# Communication.net
KiCad netlist of a schematic drawn in Altium Designer
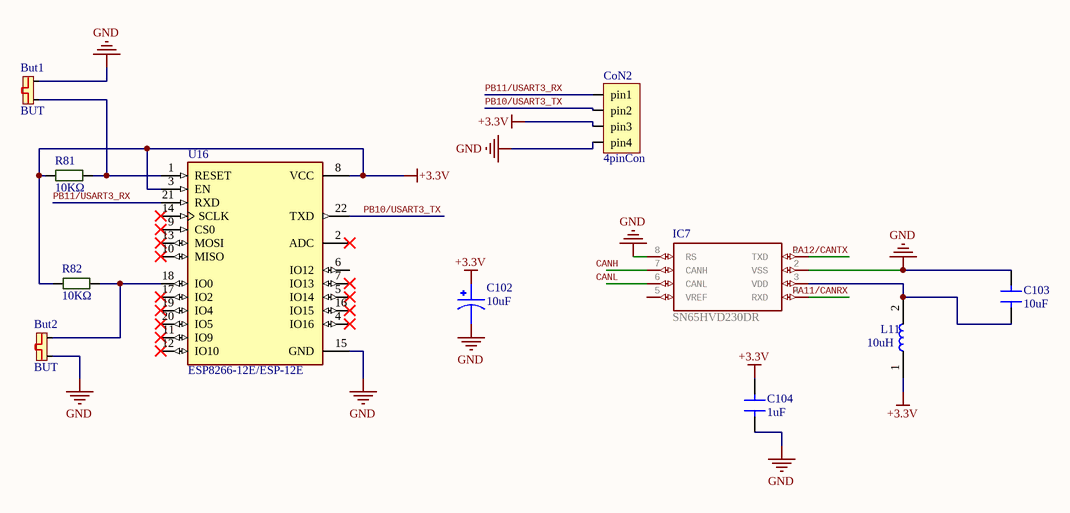
[diagram p0: Communication.SchDoc]

(export (version "E")
  (design (tool "Eeschema 10.0.6"))
  (components
    (comp (ref "But1") (value "BUT") (footprint "ButTON") (libsource (lib "Gate Driver Board") (part "BUT")))
    (comp (ref "But2") (value "BUT") (footprint "ButTON") (libsource (lib "Gate Driver Board") (part "BUT")))
    (comp (ref "C102")
      (value "10uF")
      (footprint "CapSmdElc")
      (libsource (lib "PROJE") (part "100 uF Electr Cap"))
    )
    (comp (ref "C103")
      (value "10uF")
      (footprint "C-0805")
      (libsource (lib "Gate Driver Board") (part "C-0805"))
    )
    (comp (ref "C104")
      (value "1uF")
      (footprint "C-0603W")
      (libsource (lib "Gate Driver Board") (part "C-0603"))
    )
    (comp (ref "CoN2")
      (value "4pinCon")
      (footprint "4pinCon")
      (libsource (lib "Gate Driver Board") (part "4pinCon"))
    )
    (comp (ref "IC7")
      (value "SN65HVD230DR")
      (footprint "SO08")
      (description "CAN transceiver")
      (libsource (lib "SparkFun-DigitalIC") (part "MCP2551"))
    )
    (comp (ref "L11")
      (value "10uH")
      (footprint "INDC2012X87N")
      (description "FIXED IND 10UH 300MA 884 MOHM")
      (fields (field (name "MP") "MLZ2012M100HTD25"))
      (libsource (lib "Gate Driver Board") (part "MLZ2012M100HTD25"))
    )
    (comp (ref "R81")
      (value "10KΩ")
      (footprint "R-0603R")
      (libsource (lib "Gate Driver Board") (part "R-0603"))
    )
    (comp (ref "R82")
      (value "10KΩ")
      (footprint "R-0603R")
      (libsource (lib "Gate Driver Board") (part "R-0603"))
    )
    (comp (ref "U16")
      (value "ESP8266-12E/ESP-12E")
      (footprint "XCVR_ESP8266-12E/ESP-12E")
      (fields (field (name "MF") "AI-Thinker"))
      (libsource (lib "Gate Driver Board") (part "ESP8266-12E/ESP-12E"))
    )
  )
  (nets
    (net (code "1") (name "+3.3V") (class "Default")
      (node (ref "C102") (pin "1") (pinfunction "1_1") (pintype "passive"))
      (node (ref "C104") (pin "2") (pinfunction "2_2") (pintype "passive"))
      (node (ref "CoN2") (pin "3") (pinfunction "pin3_3") (pintype "passive"))
      (node (ref "L11") (pin "1") (pinfunction "1_1") (pintype "passive"))
      (node (ref "R81") (pin "1") (pinfunction "1_1") (pintype "passive"))
      (node (ref "R82") (pin "1") (pinfunction "1_1") (pintype "passive"))
      (node (ref "U16") (pin "3") (pinfunction "EN_3") (pintype "input"))
      (node (ref "U16") (pin "8") (pinfunction "VCC_8") (pintype "power_in"))
    )
    (net (code "2") (name "/CANH") (class "Default")
      (node (ref "IC7") (pin "7") (pinfunction "CANH_7") (pintype "bidirectional"))
    )
    (net (code "3") (name "/CANL") (class "Default")
      (node (ref "IC7") (pin "6") (pinfunction "CANL_6") (pintype "bidirectional"))
    )
    (net (code "4") (name "/PA11{slash}CANRX") (class "Default")
      (node (ref "IC7") (pin "4") (pinfunction "RXD_4") (pintype "bidirectional"))
    )
    (net (code "5") (name "/PA12{slash}CANTX") (class "Default")
      (node (ref "IC7") (pin "1") (pinfunction "TXD_1") (pintype "bidirectional"))
    )
    (net (code "6") (name "/PB10{slash}USART3_TX") (class "Default")
      (node (ref "CoN2") (pin "2") (pinfunction "pin2_2") (pintype "passive"))
      (node (ref "U16") (pin "22") (pinfunction "TXD_22") (pintype "output"))
    )
    (net (code "7") (name "/PB11{slash}USART3_RX") (class "Default")
      (node (ref "CoN2") (pin "1") (pinfunction "pin1_1") (pintype "passive"))
      (node (ref "U16") (pin "21") (pinfunction "RXD_21") (pintype "input"))
    )
    (net (code "8") (name "GND") (class "Default")
      (node (ref "But1") (pin "2") (pinfunction "2_2") (pintype "passive"))
      (node (ref "But2") (pin "1") (pinfunction "1_1") (pintype "passive"))
      (node (ref "C102") (pin "2") (pinfunction "2_2") (pintype "passive"))
      (node (ref "C103") (pin "2") (pinfunction "2_2") (pintype "passive"))
      (node (ref "C104") (pin "1") (pinfunction "1_1") (pintype "passive"))
      (node (ref "CoN2") (pin "4") (pinfunction "pin4_4") (pintype "passive"))
      (node (ref "IC7") (pin "2") (pinfunction "VSS_2") (pintype "bidirectional"))
      (node (ref "IC7") (pin "8") (pinfunction "RS_8") (pintype "bidirectional"))
      (node (ref "U16") (pin "15") (pinfunction "GND_15") (pintype "power_in"))
    )
    (net (code "9") (name "Net-(IC7-VDD)") (class "Default")
      (node (ref "C103") (pin "1") (pinfunction "1_1") (pintype "passive"))
      (node (ref "IC7") (pin "3") (pinfunction "VDD_3") (pintype "bidirectional"))
      (node (ref "L11") (pin "2") (pinfunction "2_2") (pintype "passive"))
    )
    (net (code "10") (name "Net-(U16-IO0)") (class "Default")
      (node (ref "But2") (pin "2") (pinfunction "2_2") (pintype "passive"))
      (node (ref "R82") (pin "2") (pinfunction "2_2") (pintype "passive"))
      (node (ref "U16") (pin "18") (pinfunction "IO0_18") (pintype "bidirectional"))
    )
    (net (code "11") (name "Net-(U16-RESET)") (class "Default")
      (node (ref "But1") (pin "1") (pinfunction "1_1") (pintype "passive"))
      (node (ref "R81") (pin "2") (pinfunction "2_2") (pintype "passive"))
      (node (ref "U16") (pin "1") (pinfunction "RESET_1") (pintype "input"))
    )
    (net (code "12") (name "unconnected-(IC7-VREF-Pad5)") (class "Default")
      (node (ref "IC7") (pin "5") (pinfunction "VREF_5") (pintype "bidirectional"))
    )
    (net (code "13") (name "unconnected-(U16-ADC-Pad2)") (class "Default")
      (node (ref "U16") (pin "2") (pinfunction "ADC_2") (pintype "passive+no_connect"))
    )
    (net (code "14") (name "unconnected-(U16-CS0-Pad9)") (class "Default")
      (node (ref "U16") (pin "9") (pinfunction "CS0_9") (pintype "input+no_connect"))
    )
    (net (code "15") (name "unconnected-(U16-IO2-Pad17)") (class "Default")
      (node (ref "U16") (pin "17") (pinfunction "IO2_17") (pintype "bidirectional+no_connect"))
    )
    (net (code "16") (name "unconnected-(U16-IO4-Pad19)") (class "Default")
      (node (ref "U16") (pin "19") (pinfunction "IO4_19") (pintype "bidirectional+no_connect"))
    )
    (net (code "17") (name "unconnected-(U16-IO5-Pad20)") (class "Default")
      (node (ref "U16") (pin "20") (pinfunction "IO5_20") (pintype "bidirectional+no_connect"))
    )
    (net (code "18") (name "unconnected-(U16-IO9-Pad11)") (class "Default")
      (node (ref "U16") (pin "11") (pinfunction "IO9_11") (pintype "bidirectional+no_connect"))
    )
    (net (code "19") (name "unconnected-(U16-IO10-Pad12)") (class "Default")
      (node (ref "U16") (pin "12") (pinfunction "IO10_12") (pintype "bidirectional+no_connect"))
    )
    (net (code "20") (name "unconnected-(U16-IO12-Pad6)") (class "Default")
      (node (ref "U16") (pin "6") (pinfunction "IO12_6") (pintype "bidirectional"))
    )
    (net (code "21") (name "unconnected-(U16-IO13-Pad7)") (class "Default")
      (node (ref "U16") (pin "7") (pinfunction "IO13_7") (pintype "bidirectional+no_connect"))
    )
    (net (code "22") (name "unconnected-(U16-IO14-Pad5)") (class "Default")
      (node (ref "U16") (pin "5") (pinfunction "IO14_5") (pintype "bidirectional+no_connect"))
    )
    (net (code "23") (name "unconnected-(U16-IO15-Pad16)") (class "Default")
      (node (ref "U16") (pin "16") (pinfunction "IO15_16") (pintype "bidirectional+no_connect"))
    )
    (net (code "24") (name "unconnected-(U16-IO16-Pad4)") (class "Default")
      (node (ref "U16") (pin "4") (pinfunction "IO16_4") (pintype "bidirectional+no_connect"))
    )
    (net (code "25") (name "unconnected-(U16-MISO-Pad10)") (class "Default")
      (node (ref "U16") (pin "10") (pinfunction "MISO_10") (pintype "bidirectional+no_connect"))
    )
    (net (code "26") (name "unconnected-(U16-MOSI-Pad13)") (class "Default")
      (node (ref "U16") (pin "13") (pinfunction "MOSI_13") (pintype "bidirectional+no_connect"))
    )
    (net (code "27") (name "unconnected-(U16-SCLK-Pad14)") (class "Default")
      (node (ref "U16") (pin "14") (pinfunction "SCLK_14") (pintype "input+no_connect"))
    )
  )
)
